# ultimate_Co-Op_v1_0.net
KiCad netlist of a schematic drawn in EAGLE
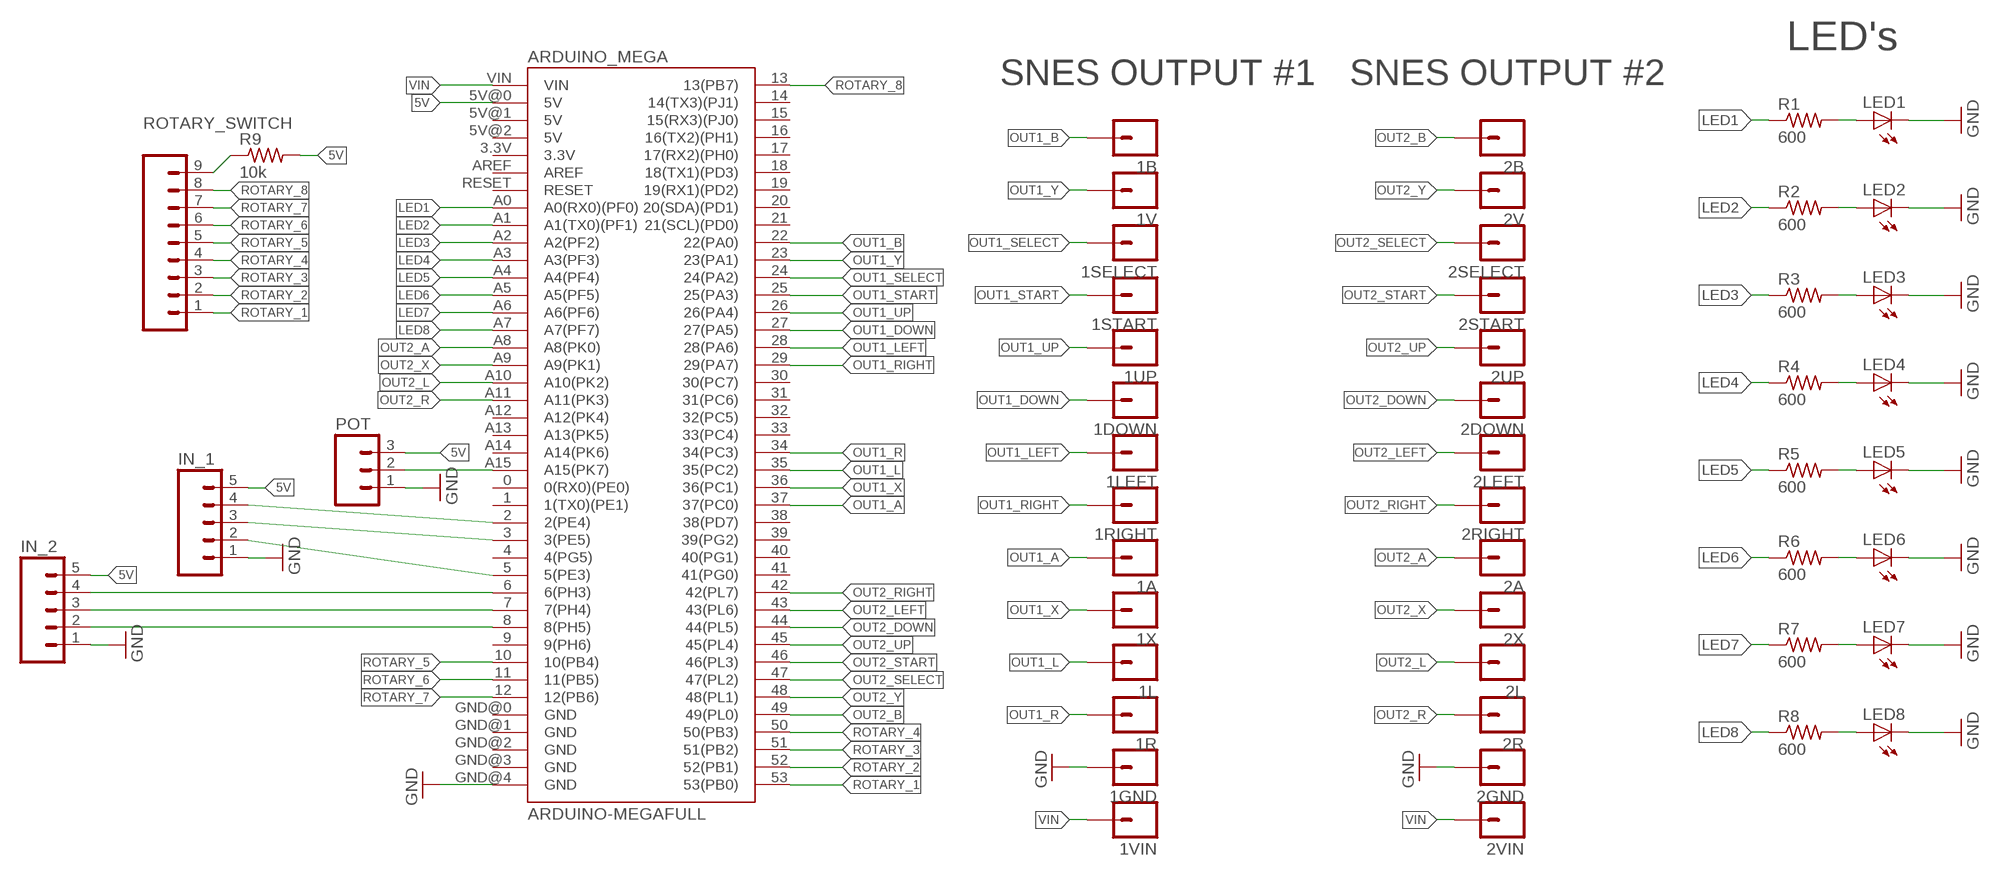
[diagram p0: schematic, sheet 1]

(export (version "E")
  (design (tool "Eeschema 10.0.6"))
  (components
    (comp (ref "1A")
      (value "M01PTH")
      (footprint "eagle-import:1X01")
      (libsource (lib "eagle-import") (part "M01PTH"))
    )
    (comp (ref "1B")
      (value "M01PTH")
      (footprint "eagle-import:1X01")
      (libsource (lib "eagle-import") (part "M01PTH"))
    )
    (comp (ref "1DOWN")
      (value "M01PTH")
      (footprint "eagle-import:1X01")
      (libsource (lib "eagle-import") (part "M01PTH"))
    )
    (comp (ref "1GND")
      (value "M01PTH")
      (footprint "eagle-import:1X01")
      (libsource (lib "eagle-import") (part "M01PTH"))
    )
    (comp (ref "1L")
      (value "M01PTH")
      (footprint "eagle-import:1X01")
      (libsource (lib "eagle-import") (part "M01PTH"))
    )
    (comp (ref "1LEFT")
      (value "M01PTH")
      (footprint "eagle-import:1X01")
      (libsource (lib "eagle-import") (part "M01PTH"))
    )
    (comp (ref "1R")
      (value "M01PTH")
      (footprint "eagle-import:1X01")
      (libsource (lib "eagle-import") (part "M01PTH"))
    )
    (comp (ref "1RIGHT")
      (value "M01PTH")
      (footprint "eagle-import:1X01")
      (libsource (lib "eagle-import") (part "M01PTH"))
    )
    (comp (ref "1SELECT")
      (value "M01PTH")
      (footprint "eagle-import:1X01")
      (libsource (lib "eagle-import") (part "M01PTH"))
    )
    (comp (ref "1START")
      (value "M01PTH")
      (footprint "eagle-import:1X01")
      (libsource (lib "eagle-import") (part "M01PTH"))
    )
    (comp (ref "1UP")
      (value "M01PTH")
      (footprint "eagle-import:1X01")
      (libsource (lib "eagle-import") (part "M01PTH"))
    )
    (comp (ref "1V")
      (value "M01PTH")
      (footprint "eagle-import:1X01")
      (libsource (lib "eagle-import") (part "M01PTH"))
    )
    (comp (ref "1VIN")
      (value "M01PTH")
      (footprint "eagle-import:1X01")
      (libsource (lib "eagle-import") (part "M01PTH"))
    )
    (comp (ref "1X")
      (value "M01PTH")
      (footprint "eagle-import:1X01")
      (libsource (lib "eagle-import") (part "M01PTH"))
    )
    (comp (ref "2A")
      (value "M01PTH")
      (footprint "eagle-import:1X01")
      (libsource (lib "eagle-import") (part "M01PTH"))
    )
    (comp (ref "2B")
      (value "M01PTH")
      (footprint "eagle-import:1X01")
      (libsource (lib "eagle-import") (part "M01PTH"))
    )
    (comp (ref "2DOWN")
      (value "M01PTH")
      (footprint "eagle-import:1X01")
      (libsource (lib "eagle-import") (part "M01PTH"))
    )
    (comp (ref "2GND")
      (value "M01PTH")
      (footprint "eagle-import:1X01")
      (libsource (lib "eagle-import") (part "M01PTH"))
    )
    (comp (ref "2L")
      (value "M01PTH")
      (footprint "eagle-import:1X01")
      (libsource (lib "eagle-import") (part "M01PTH"))
    )
    (comp (ref "2LEFT")
      (value "M01PTH")
      (footprint "eagle-import:1X01")
      (libsource (lib "eagle-import") (part "M01PTH"))
    )
    (comp (ref "2R")
      (value "M01PTH")
      (footprint "eagle-import:1X01")
      (libsource (lib "eagle-import") (part "M01PTH"))
    )
    (comp (ref "2RIGHT")
      (value "M01PTH")
      (footprint "eagle-import:1X01")
      (libsource (lib "eagle-import") (part "M01PTH"))
    )
    (comp (ref "2SELECT")
      (value "M01PTH")
      (footprint "eagle-import:1X01")
      (libsource (lib "eagle-import") (part "M01PTH"))
    )
    (comp (ref "2START")
      (value "M01PTH")
      (footprint "eagle-import:1X01")
      (libsource (lib "eagle-import") (part "M01PTH"))
    )
    (comp (ref "2UP")
      (value "M01PTH")
      (footprint "eagle-import:1X01")
      (libsource (lib "eagle-import") (part "M01PTH"))
    )
    (comp (ref "2V")
      (value "M01PTH")
      (footprint "eagle-import:1X01")
      (libsource (lib "eagle-import") (part "M01PTH"))
    )
    (comp (ref "2VIN")
      (value "M01PTH")
      (footprint "eagle-import:1X01")
      (libsource (lib "eagle-import") (part "M01PTH"))
    )
    (comp (ref "2X")
      (value "M01PTH")
      (footprint "eagle-import:1X01")
      (libsource (lib "eagle-import") (part "M01PTH"))
    )
    (comp (ref "ARDUINO_MEGA")
      (value "ARDUINO-MEGAFULL")
      (footprint "eagle-import:ARDUINO_MEGA")
      (libsource (lib "eagle-import") (part "ARDUINO-MEGAFULL"))
    )
    (comp (ref "IN_1")
      (value "M05PTH")
      (footprint "eagle-import:1X05")
      (libsource (lib "eagle-import") (part "M05PTH"))
    )
    (comp (ref "IN_2")
      (value "M05PTH")
      (footprint "eagle-import:1X05")
      (libsource (lib "eagle-import") (part "M05PTH"))
    )
    (comp (ref "LED1")
      (value "LED5MM")
      (footprint "eagle-import:LED5MM")
      (libsource (lib "eagle-import") (part "LED5MM"))
    )
    (comp (ref "LED2")
      (value "LED5MM")
      (footprint "eagle-import:LED5MM")
      (libsource (lib "eagle-import") (part "LED5MM"))
    )
    (comp (ref "LED3")
      (value "LED5MM")
      (footprint "eagle-import:LED5MM")
      (libsource (lib "eagle-import") (part "LED5MM"))
    )
    (comp (ref "LED4")
      (value "LED5MM")
      (footprint "eagle-import:LED5MM")
      (libsource (lib "eagle-import") (part "LED5MM"))
    )
    (comp (ref "LED5")
      (value "LED5MM")
      (footprint "eagle-import:LED5MM")
      (libsource (lib "eagle-import") (part "LED5MM"))
    )
    (comp (ref "LED6")
      (value "LED5MM")
      (footprint "eagle-import:LED5MM")
      (libsource (lib "eagle-import") (part "LED5MM"))
    )
    (comp (ref "LED7")
      (value "LED5MM")
      (footprint "eagle-import:LED5MM")
      (libsource (lib "eagle-import") (part "LED5MM"))
    )
    (comp (ref "LED8")
      (value "LED5MM")
      (footprint "eagle-import:LED5MM")
      (libsource (lib "eagle-import") (part "LED5MM"))
    )
    (comp (ref "POT")
      (value "M03LONGPADS")
      (footprint "eagle-import:1X03_LONGPADS")
      (libsource (lib "eagle-import") (part "M03LONGPADS"))
    )
    (comp (ref "R1")
      (value "600")
      (footprint "eagle-import:0204_7")
      (libsource (lib "eagle-import") (part "R-US_0204/7"))
    )
    (comp (ref "R2")
      (value "600")
      (footprint "eagle-import:0204_7")
      (libsource (lib "eagle-import") (part "R-US_0204/7"))
    )
    (comp (ref "R3")
      (value "600")
      (footprint "eagle-import:0204_7")
      (libsource (lib "eagle-import") (part "R-US_0204/7"))
    )
    (comp (ref "R4")
      (value "600")
      (footprint "eagle-import:0204_7")
      (libsource (lib "eagle-import") (part "R-US_0204/7"))
    )
    (comp (ref "R5")
      (value "600")
      (footprint "eagle-import:0204_7")
      (libsource (lib "eagle-import") (part "R-US_0204/7"))
    )
    (comp (ref "R6")
      (value "600")
      (footprint "eagle-import:0204_7")
      (libsource (lib "eagle-import") (part "R-US_0204/7"))
    )
    (comp (ref "R7")
      (value "600")
      (footprint "eagle-import:0204_7")
      (libsource (lib "eagle-import") (part "R-US_0204/7"))
    )
    (comp (ref "R8")
      (value "600")
      (footprint "eagle-import:0204_7")
      (libsource (lib "eagle-import") (part "R-US_0204/7"))
    )
    (comp (ref "R9")
      (value "10k")
      (footprint "eagle-import:0204_7")
      (libsource (lib "eagle-import") (part "R-US_0204/7"))
    )
    (comp (ref "ROTARY_SWITCH")
      (value "M09")
      (footprint "eagle-import:1X09")
      (libsource (lib "eagle-import") (part "M09"))
    )
  )
  (nets
    (net (code "1") (name "5V") (class "Default")
      (node (ref "ARDUINO_MEGA") (pin "5V@0") (pinfunction "5V_5V@0") (pintype "bidirectional"))
      (node (ref "IN_1") (pin "5") (pinfunction "5_5") (pintype "passive"))
      (node (ref "IN_2") (pin "5") (pinfunction "5_5") (pintype "passive"))
      (node (ref "POT") (pin "3") (pinfunction "3_3") (pintype "passive"))
      (node (ref "R9") (pin "2") (pinfunction "2_2") (pintype "passive"))
    )
    (net (code "2") (name "GND") (class "Default")
      (node (ref "1GND") (pin "1") (pinfunction "1_1") (pintype "passive"))
      (node (ref "2GND") (pin "1") (pinfunction "1_1") (pintype "passive"))
      (node (ref "ARDUINO_MEGA") (pin "GND@4") (pinfunction "GND_GND@4") (pintype "bidirectional"))
      (node (ref "IN_1") (pin "1") (pinfunction "1_1") (pintype "passive"))
      (node (ref "IN_2") (pin "1") (pinfunction "1_1") (pintype "passive"))
      (node (ref "LED1") (pin "K") (pinfunction "C_K") (pintype "passive"))
      (node (ref "LED2") (pin "K") (pinfunction "C_K") (pintype "passive"))
      (node (ref "LED3") (pin "K") (pinfunction "C_K") (pintype "passive"))
      (node (ref "LED4") (pin "K") (pinfunction "C_K") (pintype "passive"))
      (node (ref "LED5") (pin "K") (pinfunction "C_K") (pintype "passive"))
      (node (ref "LED6") (pin "K") (pinfunction "C_K") (pintype "passive"))
      (node (ref "LED7") (pin "K") (pinfunction "C_K") (pintype "passive"))
      (node (ref "LED8") (pin "K") (pinfunction "C_K") (pintype "passive"))
      (node (ref "POT") (pin "1") (pinfunction "1_1") (pintype "passive"))
    )
    (net (code "3") (name "LED1") (class "Default")
      (node (ref "ARDUINO_MEGA") (pin "A0") (pinfunction "A0(RX0)(PF0)_A0") (pintype "bidirectional"))
      (node (ref "R1") (pin "1") (pinfunction "1_1") (pintype "passive"))
    )
    (net (code "4") (name "LED2") (class "Default")
      (node (ref "ARDUINO_MEGA") (pin "A1") (pinfunction "A1(TX0)(PF1)_A1") (pintype "bidirectional"))
      (node (ref "R2") (pin "1") (pinfunction "1_1") (pintype "passive"))
    )
    (net (code "5") (name "LED3") (class "Default")
      (node (ref "ARDUINO_MEGA") (pin "A2") (pinfunction "A2(PF2)_A2") (pintype "bidirectional"))
      (node (ref "R3") (pin "1") (pinfunction "1_1") (pintype "passive"))
    )
    (net (code "6") (name "LED4") (class "Default")
      (node (ref "ARDUINO_MEGA") (pin "A3") (pinfunction "A3(PF3)_A3") (pintype "bidirectional"))
      (node (ref "R4") (pin "1") (pinfunction "1_1") (pintype "passive"))
    )
    (net (code "7") (name "LED5") (class "Default")
      (node (ref "ARDUINO_MEGA") (pin "A4") (pinfunction "A4(PF4)_A4") (pintype "bidirectional"))
      (node (ref "R5") (pin "1") (pinfunction "1_1") (pintype "passive"))
    )
    (net (code "8") (name "LED6") (class "Default")
      (node (ref "ARDUINO_MEGA") (pin "A5") (pinfunction "A5(PF5)_A5") (pintype "bidirectional"))
      (node (ref "R6") (pin "1") (pinfunction "1_1") (pintype "passive"))
    )
    (net (code "9") (name "LED7") (class "Default")
      (node (ref "ARDUINO_MEGA") (pin "A6") (pinfunction "A6(PF6)_A6") (pintype "bidirectional"))
      (node (ref "R7") (pin "1") (pinfunction "1_1") (pintype "passive"))
    )
    (net (code "10") (name "LED8") (class "Default")
      (node (ref "ARDUINO_MEGA") (pin "A7") (pinfunction "A7(PF7)_A7") (pintype "bidirectional"))
      (node (ref "R8") (pin "1") (pinfunction "1_1") (pintype "passive"))
    )
    (net (code "11") (name "Net-(ARDUINO_MEGA-2(PE4))") (class "Default")
      (node (ref "ARDUINO_MEGA") (pin "2") (pinfunction "2(PE4)_2") (pintype "bidirectional"))
      (node (ref "IN_1") (pin "4") (pinfunction "4_4") (pintype "passive"))
    )
    (net (code "12") (name "Net-(ARDUINO_MEGA-3(PE5))") (class "Default")
      (node (ref "ARDUINO_MEGA") (pin "3") (pinfunction "3(PE5)_3") (pintype "bidirectional"))
      (node (ref "IN_1") (pin "3") (pinfunction "3_3") (pintype "passive"))
    )
    (net (code "13") (name "Net-(ARDUINO_MEGA-5(PE3))") (class "Default")
      (node (ref "ARDUINO_MEGA") (pin "5") (pinfunction "5(PE3)_5") (pintype "bidirectional"))
      (node (ref "IN_1") (pin "2") (pinfunction "2_2") (pintype "passive"))
    )
    (net (code "14") (name "Net-(ARDUINO_MEGA-6(PH3))") (class "Default")
      (node (ref "ARDUINO_MEGA") (pin "6") (pinfunction "6(PH3)_6") (pintype "bidirectional"))
      (node (ref "IN_2") (pin "4") (pinfunction "4_4") (pintype "passive"))
    )
    (net (code "15") (name "Net-(ARDUINO_MEGA-7(PH4))") (class "Default")
      (node (ref "ARDUINO_MEGA") (pin "7") (pinfunction "7(PH4)_7") (pintype "bidirectional"))
      (node (ref "IN_2") (pin "3") (pinfunction "3_3") (pintype "passive"))
    )
    (net (code "16") (name "Net-(ARDUINO_MEGA-8(PH5))") (class "Default")
      (node (ref "ARDUINO_MEGA") (pin "8") (pinfunction "8(PH5)_8") (pintype "bidirectional"))
      (node (ref "IN_2") (pin "2") (pinfunction "2_2") (pintype "passive"))
    )
    (net (code "17") (name "Net-(ARDUINO_MEGA-A15(PK7))") (class "Default")
      (node (ref "ARDUINO_MEGA") (pin "A15") (pinfunction "A15(PK7)_A15") (pintype "bidirectional"))
      (node (ref "POT") (pin "2") (pinfunction "2_2") (pintype "passive"))
    )
    (net (code "18") (name "Net-(LED1-PadA)") (class "Default")
      (node (ref "LED1") (pin "A") (pinfunction "A_A") (pintype "passive"))
      (node (ref "R1") (pin "2") (pinfunction "2_2") (pintype "passive"))
    )
    (net (code "19") (name "Net-(LED2-PadA)") (class "Default")
      (node (ref "LED2") (pin "A") (pinfunction "A_A") (pintype "passive"))
      (node (ref "R2") (pin "2") (pinfunction "2_2") (pintype "passive"))
    )
    (net (code "20") (name "Net-(LED3-PadA)") (class "Default")
      (node (ref "LED3") (pin "A") (pinfunction "A_A") (pintype "passive"))
      (node (ref "R3") (pin "2") (pinfunction "2_2") (pintype "passive"))
    )
    (net (code "21") (name "Net-(LED4-PadA)") (class "Default")
      (node (ref "LED4") (pin "A") (pinfunction "A_A") (pintype "passive"))
      (node (ref "R4") (pin "2") (pinfunction "2_2") (pintype "passive"))
    )
    (net (code "22") (name "Net-(LED5-PadA)") (class "Default")
      (node (ref "LED5") (pin "A") (pinfunction "A_A") (pintype "passive"))
      (node (ref "R5") (pin "2") (pinfunction "2_2") (pintype "passive"))
    )
    (net (code "23") (name "Net-(LED6-PadA)") (class "Default")
      (node (ref "LED6") (pin "A") (pinfunction "A_A") (pintype "passive"))
      (node (ref "R6") (pin "2") (pinfunction "2_2") (pintype "passive"))
    )
    (net (code "24") (name "Net-(LED7-PadA)") (class "Default")
      (node (ref "LED7") (pin "A") (pinfunction "A_A") (pintype "passive"))
      (node (ref "R7") (pin "2") (pinfunction "2_2") (pintype "passive"))
    )
    (net (code "25") (name "Net-(LED8-PadA)") (class "Default")
      (node (ref "LED8") (pin "A") (pinfunction "A_A") (pintype "passive"))
      (node (ref "R8") (pin "2") (pinfunction "2_2") (pintype "passive"))
    )
    (net (code "26") (name "Net-(R9-Pad1)") (class "Default")
      (node (ref "R9") (pin "1") (pinfunction "1_1") (pintype "passive"))
      (node (ref "ROTARY_SWITCH") (pin "9") (pinfunction "9_9") (pintype "passive"))
    )
    (net (code "27") (name "OUT1_A") (class "Default")
      (node (ref "1A") (pin "1") (pinfunction "1_1") (pintype "passive"))
      (node (ref "ARDUINO_MEGA") (pin "37") (pinfunction "37(PC0)_37") (pintype "bidirectional"))
    )
    (net (code "28") (name "OUT1_B") (class "Default")
      (node (ref "1B") (pin "1") (pinfunction "1_1") (pintype "passive"))
      (node (ref "ARDUINO_MEGA") (pin "22") (pinfunction "22(PA0)_22") (pintype "bidirectional"))
    )
    (net (code "29") (name "OUT1_DOWN") (class "Default")
      (node (ref "1DOWN") (pin "1") (pinfunction "1_1") (pintype "passive"))
      (node (ref "ARDUINO_MEGA") (pin "27") (pinfunction "27(PA5)_27") (pintype "bidirectional"))
    )
    (net (code "30") (name "OUT1_L") (class "Default")
      (node (ref "1L") (pin "1") (pinfunction "1_1") (pintype "passive"))
      (node (ref "ARDUINO_MEGA") (pin "35") (pinfunction "35(PC2)_35") (pintype "bidirectional"))
    )
    (net (code "31") (name "OUT1_LEFT") (class "Default")
      (node (ref "1LEFT") (pin "1") (pinfunction "1_1") (pintype "passive"))
      (node (ref "ARDUINO_MEGA") (pin "28") (pinfunction "28(PA6)_28") (pintype "bidirectional"))
    )
    (net (code "32") (name "OUT1_R") (class "Default")
      (node (ref "1R") (pin "1") (pinfunction "1_1") (pintype "passive"))
      (node (ref "ARDUINO_MEGA") (pin "34") (pinfunction "34(PC3)_34") (pintype "bidirectional"))
    )
    (net (code "33") (name "OUT1_RIGHT") (class "Default")
      (node (ref "1RIGHT") (pin "1") (pinfunction "1_1") (pintype "passive"))
      (node (ref "ARDUINO_MEGA") (pin "29") (pinfunction "29(PA7)_29") (pintype "bidirectional"))
    )
    (net (code "34") (name "OUT1_SELECT") (class "Default")
      (node (ref "1SELECT") (pin "1") (pinfunction "1_1") (pintype "passive"))
      (node (ref "ARDUINO_MEGA") (pin "24") (pinfunction "24(PA2)_24") (pintype "bidirectional"))
    )
    (net (code "35") (name "OUT1_START") (class "Default")
      (node (ref "1START") (pin "1") (pinfunction "1_1") (pintype "passive"))
      (node (ref "ARDUINO_MEGA") (pin "25") (pinfunction "25(PA3)_25") (pintype "bidirectional"))
    )
    (net (code "36") (name "OUT1_UP") (class "Default")
      (node (ref "1UP") (pin "1") (pinfunction "1_1") (pintype "passive"))
      (node (ref "ARDUINO_MEGA") (pin "26") (pinfunction "26(PA4)_26") (pintype "bidirectional"))
    )
    (net (code "37") (name "OUT1_X") (class "Default")
      (node (ref "1X") (pin "1") (pinfunction "1_1") (pintype "passive"))
      (node (ref "ARDUINO_MEGA") (pin "36") (pinfunction "36(PC1)_36") (pintype "bidirectional"))
    )
    (net (code "38") (name "OUT1_Y") (class "Default")
      (node (ref "1V") (pin "1") (pinfunction "1_1") (pintype "passive"))
      (node (ref "ARDUINO_MEGA") (pin "23") (pinfunction "23(PA1)_23") (pintype "bidirectional"))
    )
    (net (code "39") (name "OUT2_A") (class "Default")
      (node (ref "2A") (pin "1") (pinfunction "1_1") (pintype "passive"))
      (node (ref "ARDUINO_MEGA") (pin "A8") (pinfunction "A8(PK0)_A8") (pintype "bidirectional"))
    )
    (net (code "40") (name "OUT2_B") (class "Default")
      (node (ref "2B") (pin "1") (pinfunction "1_1") (pintype "passive"))
      (node (ref "ARDUINO_MEGA") (pin "49") (pinfunction "49(PL0)_49") (pintype "bidirectional"))
    )
    (net (code "41") (name "OUT2_DOWN") (class "Default")
      (node (ref "2DOWN") (pin "1") (pinfunction "1_1") (pintype "passive"))
      (node (ref "ARDUINO_MEGA") (pin "44") (pinfunction "44(PL5)_44") (pintype "bidirectional"))
    )
    (net (code "42") (name "OUT2_L") (class "Default")
      (node (ref "2L") (pin "1") (pinfunction "1_1") (pintype "passive"))
      (node (ref "ARDUINO_MEGA") (pin "A10") (pinfunction "A10(PK2)_A10") (pintype "bidirectional"))
    )
    (net (code "43") (name "OUT2_LEFT") (class "Default")
      (node (ref "2LEFT") (pin "1") (pinfunction "1_1") (pintype "passive"))
      (node (ref "ARDUINO_MEGA") (pin "43") (pinfunction "43(PL6)_43") (pintype "bidirectional"))
    )
    (net (code "44") (name "OUT2_R") (class "Default")
      (node (ref "2R") (pin "1") (pinfunction "1_1") (pintype "passive"))
      (node (ref "ARDUINO_MEGA") (pin "A11") (pinfunction "A11(PK3)_A11") (pintype "bidirectional"))
    )
    (net (code "45") (name "OUT2_RIGHT") (class "Default")
      (node (ref "2RIGHT") (pin "1") (pinfunction "1_1") (pintype "passive"))
      (node (ref "ARDUINO_MEGA") (pin "42") (pinfunction "42(PL7)_42") (pintype "bidirectional"))
    )
    (net (code "46") (name "OUT2_SELECT") (class "Default")
      (node (ref "2SELECT") (pin "1") (pinfunction "1_1") (pintype "passive"))
      (node (ref "ARDUINO_MEGA") (pin "47") (pinfunction "47(PL2)_47") (pintype "bidirectional"))
    )
    (net (code "47") (name "OUT2_START") (class "Default")
      (node (ref "2START") (pin "1") (pinfunction "1_1") (pintype "passive"))
      (node (ref "ARDUINO_MEGA") (pin "46") (pinfunction "46(PL3)_46") (pintype "bidirectional"))
    )
    (net (code "48") (name "OUT2_UP") (class "Default")
      (node (ref "2UP") (pin "1") (pinfunction "1_1") (pintype "passive"))
      (node (ref "ARDUINO_MEGA") (pin "45") (pinfunction "45(PL4)_45") (pintype "bidirectional"))
    )
    (net (code "49") (name "OUT2_X") (class "Default")
      (node (ref "2X") (pin "1") (pinfunction "1_1") (pintype "passive"))
      (node (ref "ARDUINO_MEGA") (pin "A9") (pinfunction "A9(PK1)_A9") (pintype "bidirectional"))
    )
    (net (code "50") (name "OUT2_Y") (class "Default")
      (node (ref "2V") (pin "1") (pinfunction "1_1") (pintype "passive"))
      (node (ref "ARDUINO_MEGA") (pin "48") (pinfunction "48(PL1)_48") (pintype "bidirectional"))
    )
    (net (code "51") (name "ROTARY_1") (class "Default")
      (node (ref "ARDUINO_MEGA") (pin "53") (pinfunction "53(PB0)_53") (pintype "bidirectional"))
      (node (ref "ROTARY_SWITCH") (pin "1") (pinfunction "1_1") (pintype "passive"))
    )
    (net (code "52") (name "ROTARY_2") (class "Default")
      (node (ref "ARDUINO_MEGA") (pin "52") (pinfunction "52(PB1)_52") (pintype "bidirectional"))
      (node (ref "ROTARY_SWITCH") (pin "2") (pinfunction "2_2") (pintype "passive"))
    )
    (net (code "53") (name "ROTARY_3") (class "Default")
      (node (ref "ARDUINO_MEGA") (pin "51") (pinfunction "51(PB2)_51") (pintype "bidirectional"))
      (node (ref "ROTARY_SWITCH") (pin "3") (pinfunction "3_3") (pintype "passive"))
    )
    (net (code "54") (name "ROTARY_4") (class "Default")
      (node (ref "ARDUINO_MEGA") (pin "50") (pinfunction "50(PB3)_50") (pintype "bidirectional"))
      (node (ref "ROTARY_SWITCH") (pin "4") (pinfunction "4_4") (pintype "passive"))
    )
    (net (code "55") (name "ROTARY_5") (class "Default")
      (node (ref "ARDUINO_MEGA") (pin "10") (pinfunction "10(PB4)_10") (pintype "bidirectional"))
      (node (ref "ROTARY_SWITCH") (pin "5") (pinfunction "5_5") (pintype "passive"))
    )
    (net (code "56") (name "ROTARY_6") (class "Default")
      (node (ref "ARDUINO_MEGA") (pin "11") (pinfunction "11(PB5)_11") (pintype "bidirectional"))
      (node (ref "ROTARY_SWITCH") (pin "6") (pinfunction "6_6") (pintype "passive"))
    )
    (net (code "57") (name "ROTARY_7") (class "Default")
      (node (ref "ARDUINO_MEGA") (pin "12") (pinfunction "12(PB6)_12") (pintype "bidirectional"))
      (node (ref "ROTARY_SWITCH") (pin "7") (pinfunction "7_7") (pintype "passive"))
    )
    (net (code "58") (name "ROTARY_8") (class "Default")
      (node (ref "ARDUINO_MEGA") (pin "13") (pinfunction "13(PB7)_13") (pintype "bidirectional"))
      (node (ref "ROTARY_SWITCH") (pin "8") (pinfunction "8_8") (pintype "passive"))
    )
    (net (code "59") (name "VIN") (class "Default")
      (node (ref "1VIN") (pin "1") (pinfunction "1_1") (pintype "passive"))
      (node (ref "2VIN") (pin "1") (pinfunction "1_1") (pintype "passive"))
      (node (ref "ARDUINO_MEGA") (pin "VIN") (pinfunction "VIN_VIN") (pintype "bidirectional"))
    )
    (net (code "60") (name "unconnected-(ARDUINO_MEGA-0(RX0)(PE0)-Pad0)") (class "Default")
      (node (ref "ARDUINO_MEGA") (pin "0") (pinfunction "0(RX0)(PE0)_0") (pintype "bidirectional"))
    )
    (net (code "61") (name "unconnected-(ARDUINO_MEGA-1(TX0)(PE1)-Pad1)") (class "Default")
      (node (ref "ARDUINO_MEGA") (pin "1") (pinfunction "1(TX0)(PE1)_1") (pintype "bidirectional"))
    )
    (net (code "62") (name "unconnected-(ARDUINO_MEGA-4(PG5)-Pad4)") (class "Default")
      (node (ref "ARDUINO_MEGA") (pin "4") (pinfunction "4(PG5)_4") (pintype "bidirectional"))
    )
    (net (code "63") (name "unconnected-(ARDUINO_MEGA-5V-Pad5V@1)") (class "Default")
      (node (ref "ARDUINO_MEGA") (pin "5V@1") (pinfunction "5V_5V@1") (pintype "bidirectional"))
    )
    (net (code "64") (name "unconnected-(ARDUINO_MEGA-5V-Pad5V@2)") (class "Default")
      (node (ref "ARDUINO_MEGA") (pin "5V@2") (pinfunction "5V_5V@2") (pintype "bidirectional"))
    )
    (net (code "65") (name "unconnected-(ARDUINO_MEGA-9(PH6)-Pad9)") (class "Default")
      (node (ref "ARDUINO_MEGA") (pin "9") (pinfunction "9(PH6)_9") (pintype "bidirectional"))
    )
    (net (code "66") (name "unconnected-(ARDUINO_MEGA-14(TX3)(PJ1)-Pad14)") (class "Default")
      (node (ref "ARDUINO_MEGA") (pin "14") (pinfunction "14(TX3)(PJ1)_14") (pintype "bidirectional"))
    )
    (net (code "67") (name "unconnected-(ARDUINO_MEGA-15(RX3)(PJ0)-Pad15)") (class "Default")
      (node (ref "ARDUINO_MEGA") (pin "15") (pinfunction "15(RX3)(PJ0)_15") (pintype "bidirectional"))
    )
    (net (code "68") (name "unconnected-(ARDUINO_MEGA-16(TX2)(PH1)-Pad16)") (class "Default")
      (node (ref "ARDUINO_MEGA") (pin "16") (pinfunction "16(TX2)(PH1)_16") (pintype "bidirectional"))
    )
    (net (code "69") (name "unconnected-(ARDUINO_MEGA-17(RX2)(PH0)-Pad17)") (class "Default")
      (node (ref "ARDUINO_MEGA") (pin "17") (pinfunction "17(RX2)(PH0)_17") (pintype "bidirectional"))
    )
    (net (code "70") (name "unconnected-(ARDUINO_MEGA-18(TX1)(PD3)-Pad18)") (class "Default")
      (node (ref "ARDUINO_MEGA") (pin "18") (pinfunction "18(TX1)(PD3)_18") (pintype "bidirectional"))
    )
    (net (code "71") (name "unconnected-(ARDUINO_MEGA-19(RX1)(PD2)-Pad19)") (class "Default")
      (node (ref "ARDUINO_MEGA") (pin "19") (pinfunction "19(RX1)(PD2)_19") (pintype "bidirectional"))
    )
    (net (code "72") (name "unconnected-(ARDUINO_MEGA-20(SDA)(PD1)-Pad20)") (class "Default")
      (node (ref "ARDUINO_MEGA") (pin "20") (pinfunction "20(SDA)(PD1)_20") (pintype "bidirectional"))
    )
    (net (code "73") (name "unconnected-(ARDUINO_MEGA-21(SCL)(PD0)-Pad21)") (class "Default")
      (node (ref "ARDUINO_MEGA") (pin "21") (pinfunction "21(SCL)(PD0)_21") (pintype "bidirectional"))
    )
    (net (code "74") (name "unconnected-(ARDUINO_MEGA-30(PC7)-Pad30)") (class "Default")
      (node (ref "ARDUINO_MEGA") (pin "30") (pinfunction "30(PC7)_30") (pintype "bidirectional"))
    )
    (net (code "75") (name "unconnected-(ARDUINO_MEGA-31(PC6)-Pad31)") (class "Default")
      (node (ref "ARDUINO_MEGA") (pin "31") (pinfunction "31(PC6)_31") (pintype "bidirectional"))
    )
    (net (code "76") (name "unconnected-(ARDUINO_MEGA-32(PC5)-Pad32)") (class "Default")
      (node (ref "ARDUINO_MEGA") (pin "32") (pinfunction "32(PC5)_32") (pintype "bidirectional"))
    )
    (net (code "77") (name "unconnected-(ARDUINO_MEGA-33(PC4)-Pad33)") (class "Default")
      (node (ref "ARDUINO_MEGA") (pin "33") (pinfunction "33(PC4)_33") (pintype "bidirectional"))
    )
    (net (code "78") (name "unconnected-(ARDUINO_MEGA-38(PD7)-Pad38)") (class "Default")
      (node (ref "ARDUINO_MEGA") (pin "38") (pinfunction "38(PD7)_38") (pintype "bidirectional"))
    )
    (net (code "79") (name "unconnected-(ARDUINO_MEGA-39(PG2)-Pad39)") (class "Default")
      (node (ref "ARDUINO_MEGA") (pin "39") (pinfunction "39(PG2)_39") (pintype "bidirectional"))
    )
    (net (code "80") (name "unconnected-(ARDUINO_MEGA-40(PG1)-Pad40)") (class "Default")
      (node (ref "ARDUINO_MEGA") (pin "40") (pinfunction "40(PG1)_40") (pintype "bidirectional"))
    )
    (net (code "81") (name "unconnected-(ARDUINO_MEGA-41(PG0)-Pad41)") (class "Default")
      (node (ref "ARDUINO_MEGA") (pin "41") (pinfunction "41(PG0)_41") (pintype "bidirectional"))
    )
    (net (code "82") (name "unconnected-(ARDUINO_MEGA-A12(PK4)-PadA12)") (class "Default")
      (node (ref "ARDUINO_MEGA") (pin "A12") (pinfunction "A12(PK4)_A12") (pintype "bidirectional"))
    )
    (net (code "83") (name "unconnected-(ARDUINO_MEGA-A13(PK5)-PadA13)") (class "Default")
      (node (ref "ARDUINO_MEGA") (pin "A13") (pinfunction "A13(PK5)_A13") (pintype "bidirectional"))
    )
    (net (code "84") (name "unconnected-(ARDUINO_MEGA-A14(PK6)-PadA14)") (class "Default")
      (node (ref "ARDUINO_MEGA") (pin "A14") (pinfunction "A14(PK6)_A14") (pintype "bidirectional"))
    )
    (net (code "85") (name "unconnected-(ARDUINO_MEGA-GND-PadGND@0)") (class "Default")
      (node (ref "ARDUINO_MEGA") (pin "GND@0") (pinfunction "GND_GND@0") (pintype "bidirectional"))
    )
    (net (code "86") (name "unconnected-(ARDUINO_MEGA-GND-PadGND@1)") (class "Default")
      (node (ref "ARDUINO_MEGA") (pin "GND@1") (pinfunction "GND_GND@1") (pintype "bidirectional"))
    )
    (net (code "87") (name "unconnected-(ARDUINO_MEGA-GND-PadGND@2)") (class "Default")
      (node (ref "ARDUINO_MEGA") (pin "GND@2") (pinfunction "GND_GND@2") (pintype "bidirectional"))
    )
    (net (code "88") (name "unconnected-(ARDUINO_MEGA-GND-PadGND@3)") (class "Default")
      (node (ref "ARDUINO_MEGA") (pin "GND@3") (pinfunction "GND_GND@3") (pintype "bidirectional"))
    )
    (net (code "89") (name "unconnected-(ARDUINO_MEGA-Pad3.3V)") (class "Default")
      (node (ref "ARDUINO_MEGA") (pin "3.3V") (pinfunction "3.3V_3.3V") (pintype "bidirectional"))
    )
    (net (code "90") (name "unconnected-(ARDUINO_MEGA-PadAREF)") (class "Default")
      (node (ref "ARDUINO_MEGA") (pin "AREF") (pinfunction "AREF_AREF") (pintype "bidirectional"))
    )
    (net (code "91") (name "unconnected-(ARDUINO_MEGA-PadRESET)") (class "Default")
      (node (ref "ARDUINO_MEGA") (pin "RESET") (pinfunction "RESET_RESET") (pintype "bidirectional"))
    )
  )
)
